# Main_Board.net
KiCad netlist of a schematic drawn in Altium Designer
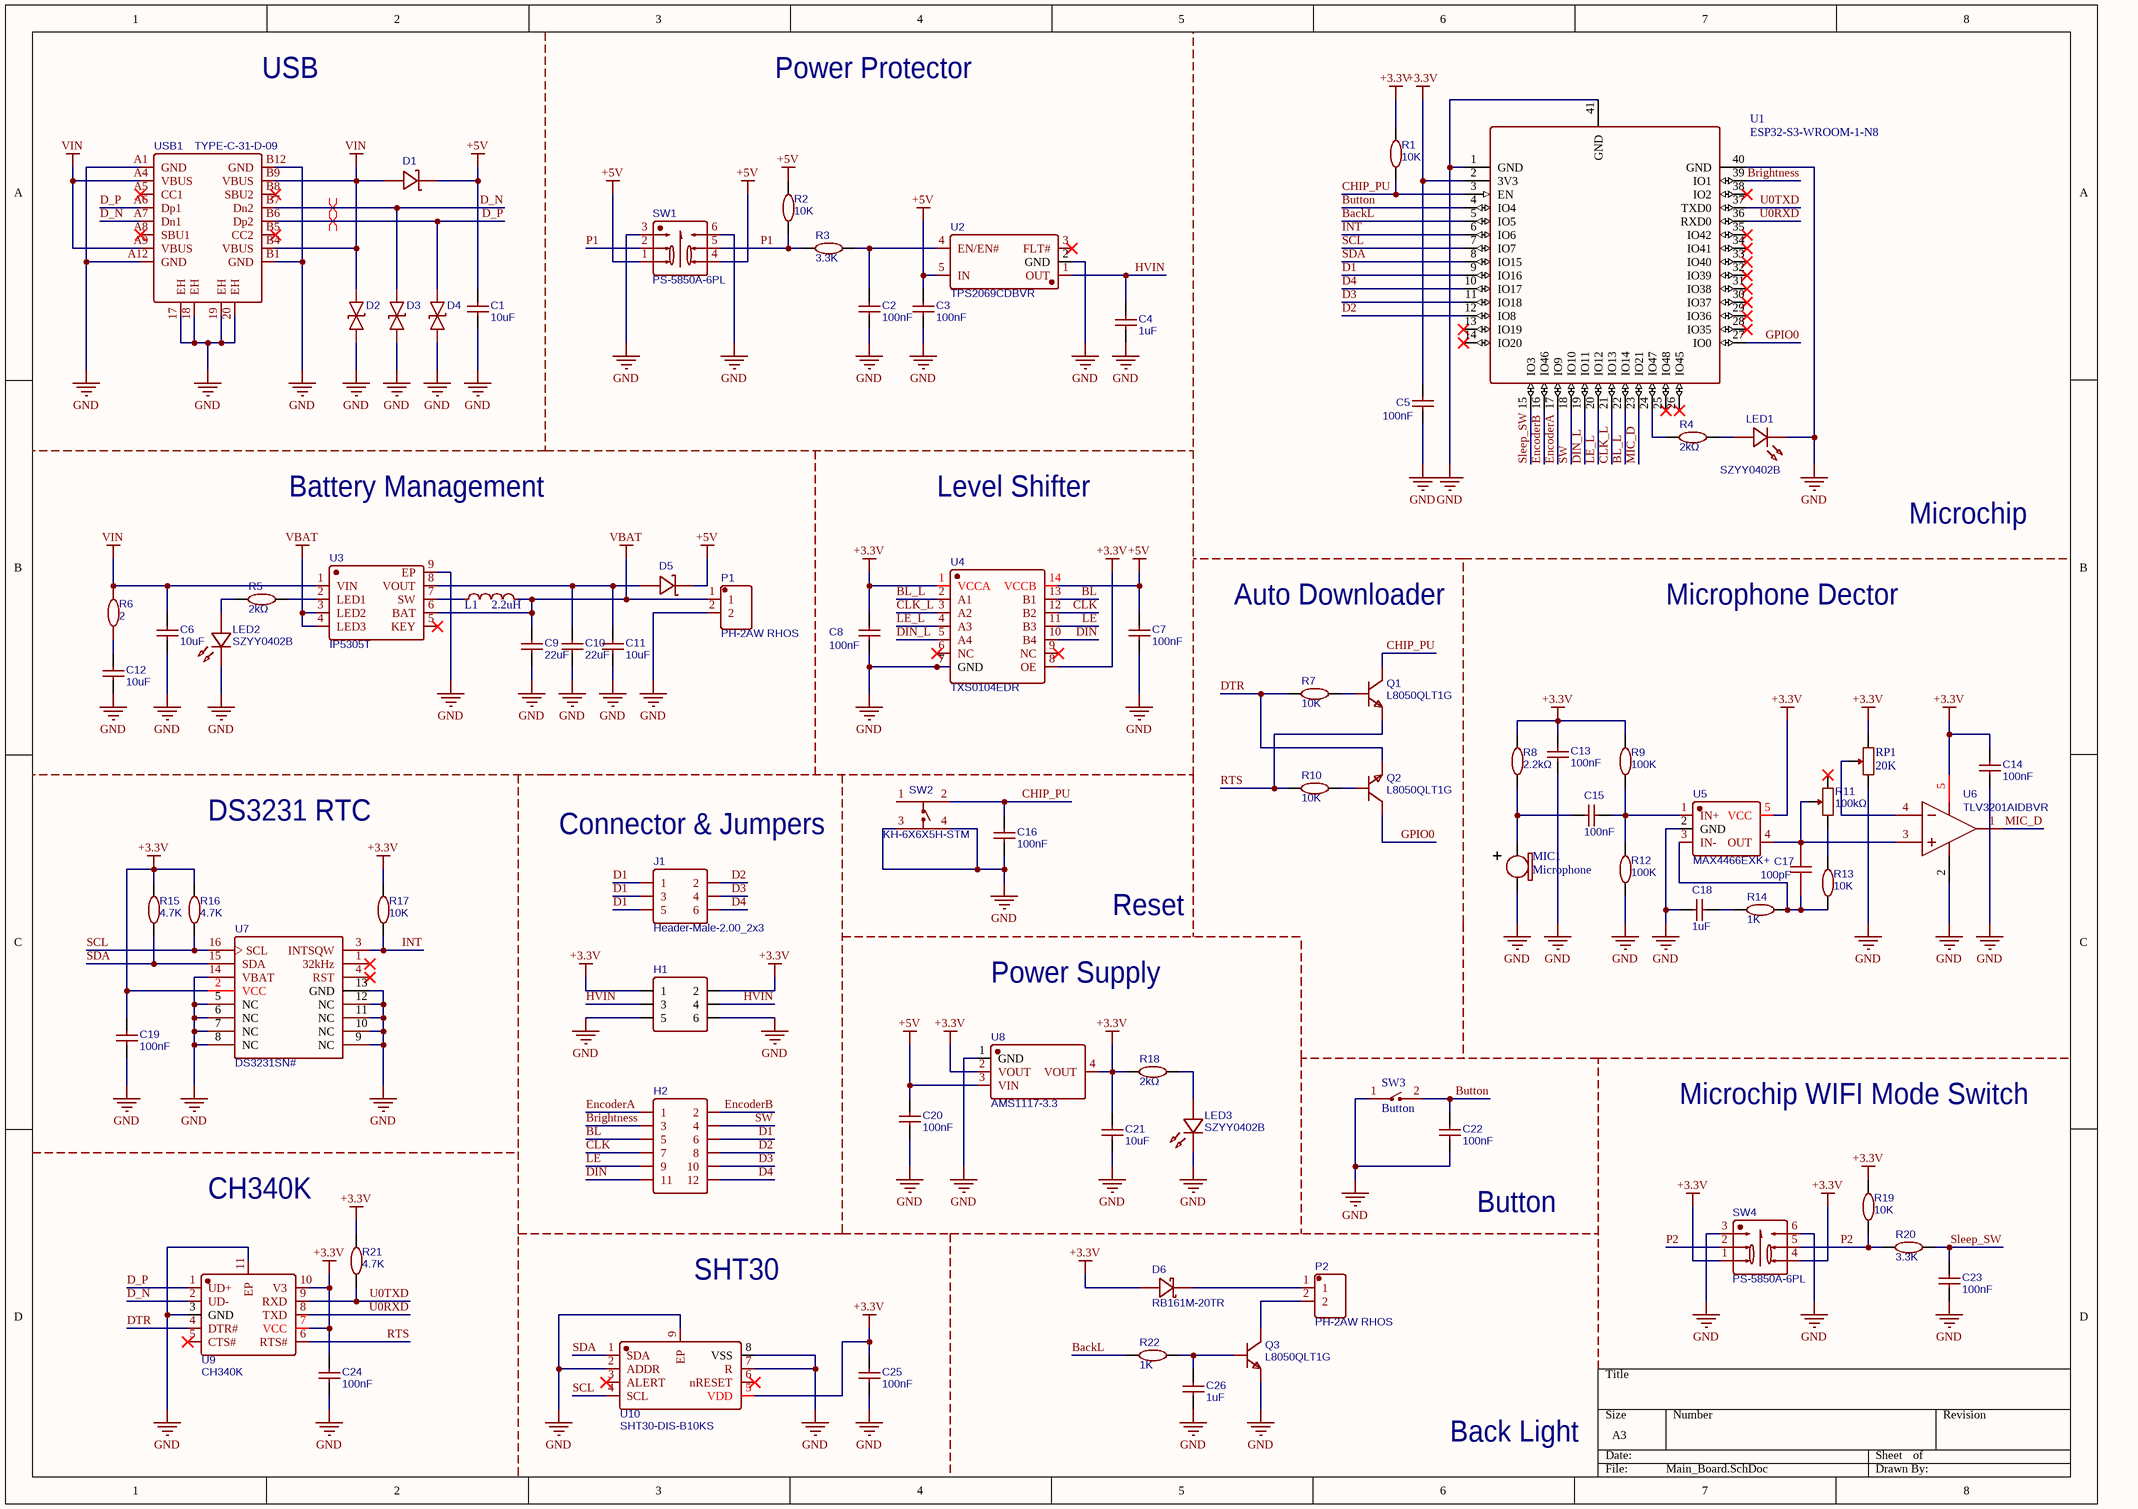
[diagram p0: Main_Board.SchDoc]

(export (version "E")
  (design (tool "Eeschema 10.0.6"))
  (components
    (comp (ref "C1")
      (value "10uF")
      (footprint "C0805")
      (fields
        (field (name "BOM_MANUFACTURER PART") "CL21A106KOQNNNE")
        (field (name "BOM_SUPPLIER PART") "C1713")
      )
      (libsource (lib "Regular_Components") (part "10uF"))
    )
    (comp (ref "C2")
      (value "100nF")
      (footprint "C0402_NEW")
      (fields
        (field (name "BOM_MANUFACTURER PART") "CL05B104KO5NNNC")
        (field (name "BOM_SUPPLIER PART") "C1525")
      )
      (libsource (lib "Regular_Components") (part "100nF"))
    )
    (comp (ref "C3")
      (value "100nF")
      (footprint "C0402_NEW")
      (fields
        (field (name "BOM_MANUFACTURER PART") "CL05B104KO5NNNC")
        (field (name "BOM_SUPPLIER PART") "C1525")
      )
      (libsource (lib "Regular_Components") (part "100nF"))
    )
    (comp (ref "C4")
      (value "1uF")
      (footprint "C0402")
      (fields
        (field (name "BOM_MANUFACTURER PART") "CL05A105KO5NNNC")
        (field (name "BOM_SUPPLIER PART") "C29266")
      )
      (libsource (lib "Regular_Components") (part "1uF"))
    )
    (comp (ref "C5")
      (value "100nF")
      (footprint "C0402_NEW")
      (fields
        (field (name "BOM_MANUFACTURER PART") "CL05B104KO5NNNC")
        (field (name "BOM_SUPPLIER PART") "C1525")
      )
      (libsource (lib "Regular_Components") (part "100nF"))
    )
    (comp (ref "C6")
      (value "10uF")
      (footprint "C0805")
      (fields
        (field (name "BOM_MANUFACTURER PART") "CL21A106KOQNNNE")
        (field (name "BOM_SUPPLIER PART") "C1713")
      )
      (libsource (lib "Regular_Components") (part "10uF"))
    )
    (comp (ref "C7")
      (value "100nF")
      (footprint "C0402_NEW")
      (fields
        (field (name "BOM_MANUFACTURER PART") "CL05B104KO5NNNC")
        (field (name "BOM_SUPPLIER PART") "C1525")
      )
      (libsource (lib "Regular_Components") (part "100nF"))
    )
    (comp (ref "C8")
      (value "100nF")
      (footprint "C0402_NEW")
      (fields
        (field (name "BOM_MANUFACTURER PART") "CL05B104KO5NNNC")
        (field (name "BOM_SUPPLIER PART") "C1525")
      )
      (libsource (lib "Regular_Components") (part "100nF"))
    )
    (comp (ref "C9")
      (value "22uF")
      (footprint "C0805")
      (fields
        (field (name "BOM_MANUFACTURER PART") "CL21A226MOQNNNE")
        (field (name "BOM_SUPPLIER PART") "C98190")
      )
      (libsource (lib "Regular_Components") (part "22uF"))
    )
    (comp (ref "C10")
      (value "22uF")
      (footprint "C0805")
      (fields
        (field (name "BOM_MANUFACTURER PART") "CL21A226MOQNNNE")
        (field (name "BOM_SUPPLIER PART") "C98190")
      )
      (libsource (lib "Regular_Components") (part "22uF"))
    )
    (comp (ref "C11")
      (value "10uF")
      (footprint "C0805")
      (fields
        (field (name "BOM_MANUFACTURER PART") "CL21A106KOQNNNE")
        (field (name "BOM_SUPPLIER PART") "C1713")
      )
      (libsource (lib "Regular_Components") (part "10uF"))
    )
    (comp (ref "C12")
      (value "10uF")
      (footprint "C0805")
      (fields
        (field (name "BOM_MANUFACTURER PART") "CL21A106KOQNNNE")
        (field (name "BOM_SUPPLIER PART") "C1713")
      )
      (libsource (lib "Regular_Components") (part "10uF"))
    )
    (comp (ref "C13")
      (value "100nF")
      (footprint "C0402_NEW")
      (fields
        (field (name "BOM_MANUFACTURER PART") "CL05B104KO5NNNC")
        (field (name "BOM_SUPPLIER PART") "C1525")
      )
      (libsource (lib "Regular_Components") (part "100nF"))
    )
    (comp (ref "C14")
      (value "100nF")
      (footprint "C0402_NEW")
      (fields
        (field (name "BOM_MANUFACTURER PART") "CL05B104KO5NNNC")
        (field (name "BOM_SUPPLIER PART") "C1525")
      )
      (libsource (lib "Regular_Components") (part "100nF"))
    )
    (comp (ref "C15")
      (value "100nF")
      (footprint "C0402_NEW")
      (fields
        (field (name "BOM_MANUFACTURER PART") "CL05B104KO5NNNC")
        (field (name "BOM_SUPPLIER PART") "C1525")
      )
      (libsource (lib "Regular_Components") (part "100nF"))
    )
    (comp (ref "C16")
      (value "100nF")
      (footprint "C0402_NEW")
      (fields
        (field (name "BOM_MANUFACTURER PART") "CL05B104KO5NNNC")
        (field (name "BOM_SUPPLIER PART") "C1525")
      )
      (libsource (lib "Regular_Components") (part "100nF"))
    )
    (comp (ref "C17")
      (value "100pF")
      (footprint "C0402")
      (fields
        (field (name "BOM_MANUFACTURER PART") "CC0402JRNPO9BN101")
        (field (name "BOM_SUPPLIER PART") "C106200")
      )
      (libsource (lib "Regular_Components") (part "100pF"))
    )
    (comp (ref "C18")
      (value "1uF")
      (footprint "C0402")
      (fields
        (field (name "BOM_MANUFACTURER PART") "CL05A105KO5NNNC")
        (field (name "BOM_SUPPLIER PART") "C29266")
      )
      (libsource (lib "Regular_Components") (part "1uF"))
    )
    (comp (ref "C19")
      (value "100nF")
      (footprint "C0402_NEW")
      (fields
        (field (name "BOM_MANUFACTURER PART") "CL05B104KO5NNNC")
        (field (name "BOM_SUPPLIER PART") "C1525")
      )
      (libsource (lib "Regular_Components") (part "100nF"))
    )
    (comp (ref "C20")
      (value "100nF")
      (footprint "C0402_NEW")
      (fields
        (field (name "BOM_MANUFACTURER PART") "CL05B104KO5NNNC")
        (field (name "BOM_SUPPLIER PART") "C1525")
      )
      (libsource (lib "Regular_Components") (part "100nF"))
    )
    (comp (ref "C21")
      (value "10uF")
      (footprint "C0805")
      (fields
        (field (name "BOM_MANUFACTURER PART") "CL21A106KOQNNNE")
        (field (name "BOM_SUPPLIER PART") "C1713")
      )
      (libsource (lib "Regular_Components") (part "10uF"))
    )
    (comp (ref "C22")
      (value "100nF")
      (footprint "C0402_NEW")
      (fields
        (field (name "BOM_MANUFACTURER PART") "CL05B104KO5NNNC")
        (field (name "BOM_SUPPLIER PART") "C1525")
      )
      (libsource (lib "Regular_Components") (part "100nF"))
    )
    (comp (ref "C23")
      (value "100nF")
      (footprint "C0402_NEW")
      (fields
        (field (name "BOM_MANUFACTURER PART") "CL05B104KO5NNNC")
        (field (name "BOM_SUPPLIER PART") "C1525")
      )
      (libsource (lib "Regular_Components") (part "100nF"))
    )
    (comp (ref "C24")
      (value "100nF")
      (footprint "C0402_NEW")
      (fields
        (field (name "BOM_MANUFACTURER PART") "CL05B104KO5NNNC")
        (field (name "BOM_SUPPLIER PART") "C1525")
      )
      (libsource (lib "Regular_Components") (part "100nF"))
    )
    (comp (ref "C25")
      (value "100nF")
      (footprint "C0402_NEW")
      (fields
        (field (name "BOM_MANUFACTURER PART") "CL05B104KO5NNNC")
        (field (name "BOM_SUPPLIER PART") "C1525")
      )
      (libsource (lib "Regular_Components") (part "100nF"))
    )
    (comp (ref "C26")
      (value "1uF")
      (footprint "C0402")
      (fields
        (field (name "BOM_MANUFACTURER PART") "CL05A105KO5NNNC")
        (field (name "BOM_SUPPLIER PART") "C29266")
      )
      (libsource (lib "Regular_Components") (part "1uF"))
    )
    (comp (ref "D1")
      (value "SS54_C22452")
      (footprint "SMA_L4.4-W2.8-LS5.4-R-RD")
      (fields (field (name "BOM_MANUFACTURER PART") "SS54") (field (name "BOM_SUPPLIER PART") "C22452"))
      (libsource (lib "Regular_Components") (part "SS54_C22452"))
    )
    (comp (ref "D2")
      (value "LESD5D5.0CT1G")
      (footprint "SOD-523_L1.2-W0.8-LS1.6-BI")
      (fields (field (name "BOM_SUPPLIER PART") "C383211") (field (name "CONTRIBUTOR") "LCSC"))
      (libsource (lib "Regular_Components") (part "LESD5D5.0CT1G"))
    )
    (comp (ref "D3")
      (value "LESD5D5.0CT1G")
      (footprint "SOD-523_L1.2-W0.8-LS1.6-BI")
      (fields (field (name "BOM_SUPPLIER PART") "C383211") (field (name "CONTRIBUTOR") "LCSC"))
      (libsource (lib "Regular_Components") (part "LESD5D5.0CT1G"))
    )
    (comp (ref "D4")
      (value "LESD5D5.0CT1G")
      (footprint "SOD-523_L1.2-W0.8-LS1.6-BI")
      (fields (field (name "BOM_SUPPLIER PART") "C383211") (field (name "CONTRIBUTOR") "LCSC"))
      (libsource (lib "Regular_Components") (part "LESD5D5.0CT1G"))
    )
    (comp (ref "D5")
      (value "SS54_C22452")
      (footprint "SMA_L4.4-W2.8-LS5.4-R-RD")
      (fields (field (name "BOM_MANUFACTURER PART") "SS54") (field (name "BOM_SUPPLIER PART") "C22452"))
      (libsource (lib "Regular_Components") (part "SS54_C22452"))
    )
    (comp (ref "D6")
      (value "RB161M-20TR")
      (footprint "SOD-123_L2.6-W1.6-LS3.5-RD-1")
      (fields (field (name "BOM_SUPPLIER PART") "C427072") (field (name "CONTRIBUTOR") "LCSC"))
      (libsource (lib "Regular_Components") (part "RB161M-20TR"))
    )
    (comp (ref "H1")
      (value "Header-Female-2.54_2x3")
      (footprint "HDR-TH_6P-P2.54-V-F-R2-C3-S2.54")
      (fields
        (field (name "BOM_MANUFACTURER PART") "DS1023-2*3SF11")
        (field (name "BOM_SUPPLIER PART") "C92272")
        (field (name "CONTRIBUTOR") "LCSC")
      )
      (libsource (lib "Regular_Components") (part "Header-Female-2.54_2x3"))
    )
    (comp (ref "H2")
      (value "Header-Female-2.54_2x6")
      (footprint "HDR-TH_12P-P2.54-V-F-R2-C6-S2.54")
      (fields (field (name "BOM_MANUFACTURER PART") "2.54-2*6P母") (field (name "BOM_SUPPLIER PART") "C36191"))
      (libsource (lib "Regular_Components") (part "Header-Female-2.54_2x6"))
    )
    (comp (ref "J1")
      (value "Header-Male-2.00_2x3")
      (footprint "HDR2.0-LI-2X3P")
      (libsource (lib "Regular_Components") (part "Header-Male-2.00_2x3"))
    )
    (comp (ref "L1")
      (value "2.2uH")
      (footprint "L_2.2uH")
      (libsource (lib "Regular_Components") (part "2.2uH"))
    )
    (comp (ref "LED1")
      (value "SZYY0402B")
      (footprint "LED0402-RD_BLUE")
      (fields (field (name "BOM_SUPPLIER PART") "C434447") (field (name "CONTRIBUTOR") "LCSC"))
      (libsource (lib "Regular_Components") (part "SZYY0402B"))
    )
    (comp (ref "LED2")
      (value "SZYY0402B")
      (footprint "LED0402-RD_BLUE")
      (fields (field (name "BOM_SUPPLIER PART") "C434447") (field (name "CONTRIBUTOR") "LCSC"))
      (libsource (lib "Regular_Components") (part "SZYY0402B"))
    )
    (comp (ref "LED3")
      (value "SZYY0402B")
      (footprint "LED0402-RD_BLUE")
      (fields (field (name "BOM_SUPPLIER PART") "C434447") (field (name "CONTRIBUTOR") "LCSC"))
      (libsource (lib "Regular_Components") (part "SZYY0402B"))
    )
    (comp (ref "MIC1")
      (value "Microphone")
      (footprint "Microphone")
      (libsource (lib "Regular_Components") (part "Microphone"))
    )
    (comp (ref "P1")
      (value "PH-2AW RHOS")
      (footprint "CONN-TH_2P-P2.00_PH-2AW")
      (fields (field (name "BOM_SUPPLIER PART") "C16965"))
      (libsource (lib "Regular_Components") (part "PH-2AW RHOS"))
    )
    (comp (ref "P2")
      (value "PH-2AW RHOS")
      (footprint "CONN-TH_2P-P2.00_PH-2AW")
      (fields (field (name "BOM_SUPPLIER PART") "C16965"))
      (libsource (lib "Regular_Components") (part "PH-2AW RHOS"))
    )
    (comp (ref "Q1")
      (value "L8050QLT1G")
      (footprint "SOT-23-3_L2.9-W1.3-P1.90-LS2.4-BR")
      (fields (field (name "BOM_SUPPLIER PART") "C49581"))
      (libsource (lib "Regular_Components") (part "L8050QLT1G"))
    )
    (comp (ref "Q2")
      (value "L8050QLT1G")
      (footprint "SOT-23-3_L2.9-W1.3-P1.90-LS2.4-BR")
      (fields (field (name "BOM_SUPPLIER PART") "C49581"))
      (libsource (lib "Regular_Components") (part "L8050QLT1G"))
    )
    (comp (ref "Q3")
      (value "L8050QLT1G")
      (footprint "SOT-23-3_L2.9-W1.3-P1.90-LS2.4-BR")
      (fields (field (name "BOM_SUPPLIER PART") "C49581"))
      (libsource (lib "Regular_Components") (part "L8050QLT1G"))
    )
    (comp (ref "R1")
      (value "10K")
      (footprint "R0402")
      (fields
        (field (name "BOM_MANUFACTURER PART") "RC0402FR-0710KL")
        (field (name "BOM_SUPPLIER PART") "C60490")
      )
      (libsource (lib "Regular_Components") (part "10K"))
    )
    (comp (ref "R2")
      (value "10K")
      (footprint "R0402")
      (fields
        (field (name "BOM_MANUFACTURER PART") "RC0402FR-0710KL")
        (field (name "BOM_SUPPLIER PART") "C60490")
      )
      (libsource (lib "Regular_Components") (part "10K"))
    )
    (comp (ref "R3")
      (value "3.3K")
      (footprint "R0402")
      (fields
        (field (name "BOM_MANUFACTURER PART") "RC0402FR-073K3L")
        (field (name "BOM_SUPPLIER PART") "C137992")
      )
      (libsource (lib "Regular_Components") (part "3.3K"))
    )
    (comp (ref "R4")
      (value "2kΩ")
      (footprint "R0402")
      (fields
        (field (name "BOM_MANUFACTURER PART") "0402WGF2001TCE")
        (field (name "BOM_SUPPLIER PART") "C4109")
      )
      (libsource (lib "Regular_Components") (part "2kΩ"))
    )
    (comp (ref "R5")
      (value "2kΩ")
      (footprint "R0402")
      (fields
        (field (name "BOM_MANUFACTURER PART") "0402WGF2001TCE")
        (field (name "BOM_SUPPLIER PART") "C4109")
      )
      (libsource (lib "Regular_Components") (part "2kΩ"))
    )
    (comp (ref "R6")
      (value "2")
      (footprint "R0603")
      (fields
        (field (name "BOM_SUPPLIER PART") "C185341")
        (field (name "BOM_MANUFACTURER PART") "RC0603FR-072RL")
        (field (name "CONTRIBUTOR") "LCSC")
      )
      (libsource (lib "Regular_Components") (part "2"))
    )
    (comp (ref "R7")
      (value "10K")
      (footprint "R0402")
      (fields
        (field (name "BOM_MANUFACTURER PART") "RC0402FR-0710KL")
        (field (name "BOM_SUPPLIER PART") "C60490")
      )
      (libsource (lib "Regular_Components") (part "10K"))
    )
    (comp (ref "R8")
      (value "2.2kΩ")
      (footprint "R0402")
      (fields
        (field (name "BOM_MANUFACTURER PART") "0402WGF2001TCE")
        (field (name "BOM_SUPPLIER PART") "C4109")
      )
      (libsource (lib "Regular_Components") (part "2kΩ"))
    )
    (comp (ref "R9")
      (value "100K")
      (footprint "R0402")
      (fields
        (field (name "BOM_MANUFACTURER PART") "RC0402FR-07100KL")
        (field (name "BOM_SUPPLIER PART") "C60491")
      )
      (libsource (lib "Regular_Components") (part "100K"))
    )
    (comp (ref "R10")
      (value "10K")
      (footprint "R0402")
      (fields
        (field (name "BOM_MANUFACTURER PART") "RC0402FR-0710KL")
        (field (name "BOM_SUPPLIER PART") "C60490")
      )
      (libsource (lib "Regular_Components") (part "10K"))
    )
    (comp (ref "R11")
      (value "100kΩ")
      (footprint "RES-ADJ-SMD_VG039NCH")
      (fields
        (field (name "BOM_MANUFACTURER PART") "VG039NCHXTB104")
        (field (name "BOM_SUPPLIER PART") "C128545")
        (field (name "CONTRIBUTOR") "LCSC")
      )
      (libsource (lib "Regular_Components") (part "RP-VG039NCHXTB104"))
    )
    (comp (ref "R12")
      (value "100K")
      (footprint "R0402")
      (fields
        (field (name "BOM_MANUFACTURER PART") "RC0402FR-07100KL")
        (field (name "BOM_SUPPLIER PART") "C60491")
      )
      (libsource (lib "Regular_Components") (part "100K"))
    )
    (comp (ref "R13")
      (value "10K")
      (footprint "R0402")
      (fields
        (field (name "BOM_MANUFACTURER PART") "RC0402FR-0710KL")
        (field (name "BOM_SUPPLIER PART") "C60490")
      )
      (libsource (lib "Regular_Components") (part "10K"))
    )
    (comp (ref "R14")
      (value "1K")
      (footprint "R0402")
      (fields
        (field (name "BOM_MANUFACTURER PART") "RC0402FR-071KL")
        (field (name "BOM_SUPPLIER PART") "C106235")
      )
      (libsource (lib "Regular_Components") (part "1K"))
    )
    (comp (ref "R15")
      (value "4.7K")
      (footprint "R0402")
      (fields
        (field (name "BOM_MANUFACTURER PART") "RC0402FR-074K7L")
        (field (name "BOM_SUPPLIER PART") "C105871")
      )
      (libsource (lib "Regular_Components") (part "4.7K"))
    )
    (comp (ref "R16")
      (value "4.7K")
      (footprint "R0402")
      (fields
        (field (name "BOM_MANUFACTURER PART") "RC0402FR-074K7L")
        (field (name "BOM_SUPPLIER PART") "C105871")
      )
      (libsource (lib "Regular_Components") (part "4.7K"))
    )
    (comp (ref "R17")
      (value "10K")
      (footprint "R0402")
      (fields
        (field (name "BOM_MANUFACTURER PART") "RC0402FR-0710KL")
        (field (name "BOM_SUPPLIER PART") "C60490")
      )
      (libsource (lib "Regular_Components") (part "10K"))
    )
    (comp (ref "R18")
      (value "2kΩ")
      (footprint "R0402")
      (fields
        (field (name "BOM_MANUFACTURER PART") "0402WGF2001TCE")
        (field (name "BOM_SUPPLIER PART") "C4109")
      )
      (libsource (lib "Regular_Components") (part "2kΩ"))
    )
    (comp (ref "R19")
      (value "10K")
      (footprint "R0402")
      (fields
        (field (name "BOM_MANUFACTURER PART") "RC0402FR-0710KL")
        (field (name "BOM_SUPPLIER PART") "C60490")
      )
      (libsource (lib "Regular_Components") (part "10K"))
    )
    (comp (ref "R20")
      (value "3.3K")
      (footprint "R0402")
      (fields
        (field (name "BOM_MANUFACTURER PART") "RC0402FR-073K3L")
        (field (name "BOM_SUPPLIER PART") "C137992")
      )
      (libsource (lib "Regular_Components") (part "3.3K"))
    )
    (comp (ref "R21")
      (value "4.7K")
      (footprint "R0402")
      (fields
        (field (name "BOM_MANUFACTURER PART") "RC0402FR-074K7L")
        (field (name "BOM_SUPPLIER PART") "C105871")
      )
      (libsource (lib "Regular_Components") (part "4.7K"))
    )
    (comp (ref "R22")
      (value "1K")
      (footprint "R0402")
      (fields
        (field (name "BOM_MANUFACTURER PART") "RC0402FR-071KL")
        (field (name "BOM_SUPPLIER PART") "C106235")
      )
      (libsource (lib "Regular_Components") (part "1K"))
    )
    (comp (ref "RP1")
      (value "20K")
      (footprint "RES-ADJ-SMD_VG039NCH")
      (fields (field (name "版权归属") "源创客"))
      (libsource (lib "Regular_Components") (part "RP-VG039NCHXTB203"))
    )
    (comp (ref "SW1")
      (value "PS-5850A-6PL")
      (footprint "SW-TH_6P-L5.8-W5.8-P2.00-LS4.5-BL")
      (fields (field (name "BOM_SUPPLIER PART") "C963201") (field (name "CONTRIBUTOR") "LCSC"))
      (libsource (lib "Regular_Components") (part "PS-5850A-6PL"))
    )
    (comp (ref "SW2")
      (value "KH-6X6X5H-STM")
      (footprint "SW-SMD_4P-L6.0-W6.0-P4.50-LS9.0-2")
      (fields (field (name "BOM_SUPPLIER PART") "C2837531") (field (name "CONTRIBUTOR") "LCSC"))
      (libsource (lib "Regular_Components") (part "KH-6X6X5H-STM"))
    )
    (comp (ref "SW3")
      (value "Button")
      (footprint "Button")
      (libsource (lib "Regular_Components") (part "Button"))
    )
    (comp (ref "SW4")
      (value "PS-5850A-6PL")
      (footprint "SW-TH_6P-L5.8-W5.8-P2.00-LS4.5-BL")
      (fields (field (name "BOM_SUPPLIER PART") "C963201") (field (name "CONTRIBUTOR") "LCSC"))
      (libsource (lib "Regular_Components") (part "PS-5850A-6PL"))
    )
    (comp (ref "U1")
      (value "ESP32-S3-WROOM-1-N8")
      (footprint "ESP32-S3-WROOM-1-N8_EXP")
      (fields (field (name "COPYRIGHT") "Copyright (C) 2023 Ultra Librarian. All rights reserved."))
      (libsource (lib "Regular_Components") (part "ESP32-S3-WROOM-1-N8"))
    )
    (comp (ref "U2")
      (value "TPS2069CDBVR")
      (footprint "SOT-23-5_L3.0-W1.7-P0.95-LS2.8-BR")
      (fields (field (name "BOM_SUPPLIER PART") "C181752") (field (name "CONTRIBUTOR") "LCSC"))
      (libsource (lib "Regular_Components") (part "TPS2069CDBVR"))
    )
    (comp (ref "U3")
      (value "IP5305T")
      (footprint "ESOP-8_L4.9-W3.9-P1.27-LS6.0-BL-EP")
      (fields (field (name "BOM_SUPPLIER PART") "C2982924") (field (name "CONTRIBUTOR") "LCSC"))
      (libsource (lib "Regular_Components") (part "IP5305T"))
    )
    (comp (ref "U4")
      (value "TXS0104EDR")
      (footprint "SOIC-14_L8.7-W3.9-P1.27-LS6.0-BL")
      (fields (field (name "BOM_SUPPLIER PART") "C79342") (field (name "CONTRIBUTOR") "LCSC"))
      (libsource (lib "Regular_Components") (part "TXS0104EDR"))
    )
    (comp (ref "U5")
      (value "MAX4466EXK+")
      (footprint "SC-70-5_L2.0-W1.3-P0.65-LS2.2-BL")
      (fields (field (name "BOM_SUPPLIER PART") "C2892801") (field (name "CONTRIBUTOR") "LCSC"))
      (libsource (lib "Regular_Components") (part "MAX4466EXK+"))
    )
    (comp (ref "U6")
      (value "TLV3201AIDBVR")
      (footprint "SOT-23-5_L3.0-W1.7-P0.95-LS2.8-BR")
      (fields (field (name "BOM_SUPPLIER PART") "C105188"))
      (libsource (lib "Regular_Components") (part "TLV3201AIDBVR"))
    )
    (comp (ref "U7")
      (value "DS3231SN#")
      (footprint "SOIC-16_L10.3-W7.5-P1.27-LS10.3-BL")
      (fields
        (field (name "BOM_SUPPLIER PART") "C9866")
        (field (name "BOM_MANUFACTURER PART") "DS3231SN#T&R")
        (field (name "SUBPART_NO") "1")
      )
      (libsource (lib "Regular_Components") (part "DS3231SN#"))
    )
    (comp (ref "U8")
      (value "AMS1117-3.3")
      (footprint "SOT-223-3_L6.5-W3.4-P2.30-LS7.0-BR")
      (fields (field (name "BOM_SUPPLIER PART") "C6186"))
      (libsource (lib "Regular_Components") (part "AMS1117-3.3"))
    )
    (comp (ref "U9")
      (value "CH340K")
      (footprint "ESOP-10_L4.9-W3.9-P1.00-LS6.2-BL-EP")
      (fields (field (name "BOM_SUPPLIER PART") "C968586") (field (name "CONTRIBUTOR") "LCSC"))
      (libsource (lib "Regular_Components") (part "CH340K"))
    )
    (comp (ref "U10")
      (value "SHT30-DIS-B10KS")
      (footprint "DFN-8_L2.5-W2.5-P0.50-BL-EP")
      (fields (field (name "BOM_SUPPLIER PART") "C2687423") (field (name "CONTRIBUTOR") "LCSC"))
      (libsource (lib "Regular_Components") (part "SHT30-DIS-B10KS"))
    )
    (comp (ref "USB1")
      (value "TYPE-C-31-D-09")
      (footprint "USB-C-TH_TYPE-C-31-D-09")
      (fields (field (name "BOM_SUPPLIER PART") "C2848615") (field (name "CONTRIBUTOR") "LCSC"))
      (libsource (lib "Regular_Components") (part "TYPE-C-31-D-09"))
    )
  )
  (nets
    (net (code "1") (name "+3.3V") (class "Default")
      (node (ref "C13") (pin "2") (pinfunction "2_2") (pintype "passive"))
      (node (ref "C14") (pin "2") (pinfunction "2_2") (pintype "passive"))
      (node (ref "C19") (pin "2") (pinfunction "2_2") (pintype "passive"))
      (node (ref "C21") (pin "2") (pinfunction "2_2") (pintype "passive"))
      (node (ref "C24") (pin "2") (pinfunction "2_2") (pintype "passive"))
      (node (ref "C25") (pin "2") (pinfunction "2_2") (pintype "passive"))
      (node (ref "C5") (pin "2") (pinfunction "2_2") (pintype "passive"))
      (node (ref "C8") (pin "2") (pinfunction "2_2") (pintype "passive"))
      (node (ref "D6") (pin "2") (pinfunction "A_2") (pintype "passive"))
      (node (ref "H1") (pin "1") (pinfunction "1_1") (pintype "passive"))
      (node (ref "H1") (pin "2") (pinfunction "2_2") (pintype "passive"))
      (node (ref "R1") (pin "2") (pinfunction "2_2") (pintype "passive"))
      (node (ref "R15") (pin "2") (pinfunction "2_2") (pintype "passive"))
      (node (ref "R16") (pin "2") (pinfunction "2_2") (pintype "passive"))
      (node (ref "R17") (pin "2") (pinfunction "2_2") (pintype "passive"))
      (node (ref "R18") (pin "1") (pinfunction "1_1") (pintype "passive"))
      (node (ref "R19") (pin "2") (pinfunction "2_2") (pintype "passive"))
      (node (ref "R21") (pin "2") (pinfunction "2_2") (pintype "passive"))
      (node (ref "R8") (pin "2") (pinfunction "2_2") (pintype "passive"))
      (node (ref "R9") (pin "2") (pinfunction "2_2") (pintype "passive"))
      (node (ref "RP1") (pin "1") (pinfunction "1_1") (pintype "passive"))
      (node (ref "SW4") (pin "1") (pinfunction "1_1") (pintype "passive"))
      (node (ref "SW4") (pin "4") (pinfunction "4_4") (pintype "passive"))
      (node (ref "U1") (pin "2") (pinfunction "3V3_2") (pintype "power_in"))
      (node (ref "U10") (pin "5") (pinfunction "VDD_5") (pintype "passive"))
      (node (ref "U4") (pin "1") (pinfunction "VCCA_1") (pintype "passive"))
      (node (ref "U4") (pin "8") (pinfunction "OE_8") (pintype "passive"))
      (node (ref "U5") (pin "5") (pinfunction "VCC_5") (pintype "passive"))
      (node (ref "U6") (pin "5") (pinfunction "VCC_5") (pintype "passive"))
      (node (ref "U7") (pin "2") (pinfunction "VCC_2") (pintype "passive"))
      (node (ref "U8") (pin "2") (pinfunction "VOUT_2") (pintype "passive"))
      (node (ref "U8") (pin "4") (pinfunction "VOUT_4") (pintype "passive"))
      (node (ref "U9") (pin "10") (pinfunction "V3_10") (pintype "passive"))
      (node (ref "U9") (pin "7") (pinfunction "VCC_7") (pintype "passive"))
    )
    (net (code "2") (name "+5V") (class "Default")
      (node (ref "C1") (pin "2") (pinfunction "2_2") (pintype "passive"))
      (node (ref "C20") (pin "2") (pinfunction "2_2") (pintype "passive"))
      (node (ref "C3") (pin "2") (pinfunction "2_2") (pintype "passive"))
      (node (ref "C7") (pin "2") (pinfunction "2_2") (pintype "passive"))
      (node (ref "D1") (pin "2") (pinfunction "K_2") (pintype "passive"))
      (node (ref "D5") (pin "2") (pinfunction "K_2") (pintype "passive"))
      (node (ref "R2") (pin "2") (pinfunction "2_2") (pintype "passive"))
      (node (ref "SW1") (pin "1") (pinfunction "1_1") (pintype "passive"))
      (node (ref "SW1") (pin "4") (pinfunction "4_4") (pintype "passive"))
      (node (ref "U2") (pin "5") (pinfunction "IN_5") (pintype "passive"))
      (node (ref "U4") (pin "14") (pinfunction "VCCB_14") (pintype "passive"))
      (node (ref "U8") (pin "3") (pinfunction "VIN_3") (pintype "passive"))
    )
    (net (code "3") (name "/BL") (class "Default")
      (node (ref "H2") (pin "5") (pinfunction "5_5") (pintype "passive"))
      (node (ref "U4") (pin "13") (pinfunction "B1_13") (pintype "passive"))
    )
    (net (code "4") (name "/BL_L") (class "Default")
      (node (ref "U1") (pin "22") (pinfunction "IO14_22") (pintype "bidirectional"))
      (node (ref "U4") (pin "2") (pinfunction "A1_2") (pintype "passive"))
    )
    (net (code "5") (name "/BackL") (class "Default")
      (node (ref "R22") (pin "1") (pinfunction "1_1") (pintype "passive"))
      (node (ref "U1") (pin "5") (pinfunction "IO5_5") (pintype "bidirectional"))
    )
    (net (code "6") (name "/Brightness") (class "Default")
      (node (ref "H2") (pin "3") (pinfunction "3_3") (pintype "passive"))
      (node (ref "U1") (pin "39") (pinfunction "IO1_39") (pintype "bidirectional"))
    )
    (net (code "7") (name "/Button") (class "Default")
      (node (ref "C22") (pin "2") (pinfunction "2_2") (pintype "passive"))
      (node (ref "SW3") (pin "2") (pinfunction "2_2") (pintype "passive"))
      (node (ref "U1") (pin "4") (pinfunction "IO4_4") (pintype "bidirectional"))
    )
    (net (code "8") (name "/CHIP_PU") (class "Default")
      (node (ref "C16") (pin "2") (pinfunction "2_2") (pintype "passive"))
      (node (ref "Q1") (pin "3") (pinfunction "C_3") (pintype "passive"))
      (node (ref "R1") (pin "1") (pinfunction "1_1") (pintype "passive"))
      (node (ref "SW2") (pin "2") (pinfunction "2_2") (pintype "passive"))
      (node (ref "U1") (pin "3") (pinfunction "EN_3") (pintype "input"))
    )
    (net (code "9") (name "/CLK") (class "Default")
      (node (ref "H2") (pin "7") (pinfunction "7_7") (pintype "passive"))
      (node (ref "U4") (pin "12") (pinfunction "B2_12") (pintype "passive"))
    )
    (net (code "10") (name "/CLK_L") (class "Default")
      (node (ref "U1") (pin "21") (pinfunction "IO13_21") (pintype "bidirectional"))
      (node (ref "U4") (pin "3") (pinfunction "A2_3") (pintype "passive"))
    )
    (net (code "11") (name "/D1") (class "Default")
      (node (ref "H2") (pin "6") (pinfunction "6_6") (pintype "passive"))
      (node (ref "J1") (pin "1") (pinfunction "1_1") (pintype "passive"))
      (node (ref "J1") (pin "3") (pinfunction "3_3") (pintype "passive"))
      (node (ref "J1") (pin "5") (pinfunction "5_5") (pintype "passive"))
      (node (ref "U1") (pin "9") (pinfunction "IO16_9") (pintype "bidirectional"))
    )
    (net (code "12") (name "/D2") (class "Default")
      (node (ref "H2") (pin "8") (pinfunction "8_8") (pintype "passive"))
      (node (ref "J1") (pin "2") (pinfunction "2_2") (pintype "passive"))
      (node (ref "U1") (pin "12") (pinfunction "IO8_12") (pintype "bidirectional"))
    )
    (net (code "13") (name "/D3") (class "Default")
      (node (ref "H2") (pin "10") (pinfunction "10_10") (pintype "passive"))
      (node (ref "J1") (pin "4") (pinfunction "4_4") (pintype "passive"))
      (node (ref "U1") (pin "11") (pinfunction "IO18_11") (pintype "bidirectional"))
    )
    (net (code "14") (name "/D4") (class "Default")
      (node (ref "H2") (pin "12") (pinfunction "12_12") (pintype "passive"))
      (node (ref "J1") (pin "6") (pinfunction "6_6") (pintype "passive"))
      (node (ref "U1") (pin "10") (pinfunction "IO17_10") (pintype "bidirectional"))
    )
    (net (code "15") (name "/DIN") (class "Default")
      (node (ref "H2") (pin "11") (pinfunction "11_11") (pintype "passive"))
      (node (ref "U4") (pin "10") (pinfunction "B4_10") (pintype "passive"))
    )
    (net (code "16") (name "/DIN_L") (class "Default")
      (node (ref "U1") (pin "19") (pinfunction "IO11_19") (pintype "bidirectional"))
      (node (ref "U4") (pin "5") (pinfunction "A4_5") (pintype "passive"))
    )
    (net (code "17") (name "/DTR") (class "Default")
      (node (ref "Q2") (pin "2") (pinfunction "E_2") (pintype "passive"))
      (node (ref "R7") (pin "1") (pinfunction "1_1") (pintype "passive"))
      (node (ref "U9") (pin "4") (pinfunction "DTR#_4") (pintype "passive"))
    )
    (net (code "18") (name "/D_N") (class "Default")
      (node (ref "D3") (pin "2") (pinfunction "2_2") (pintype "passive"))
      (node (ref "U9") (pin "2") (pinfunction "UD-_2") (pintype "passive"))
      (node (ref "USB1") (pin "A7") (pinfunction "Dn1_A7") (pintype "passive"))
      (node (ref "USB1") (pin "B7") (pinfunction "Dn2_B7") (pintype "passive"))
    )
    (net (code "19") (name "/D_P") (class "Default")
      (node (ref "D4") (pin "2") (pinfunction "2_2") (pintype "passive"))
      (node (ref "U9") (pin "1") (pinfunction "UD+_1") (pintype "passive"))
      (node (ref "USB1") (pin "A6") (pinfunction "Dp1_A6") (pintype "passive"))
      (node (ref "USB1") (pin "B6") (pinfunction "Dp2_B6") (pintype "passive"))
    )
    (net (code "20") (name "/EncoderA") (class "Default")
      (node (ref "H2") (pin "1") (pinfunction "1_1") (pintype "passive"))
      (node (ref "U1") (pin "17") (pinfunction "IO9_17") (pintype "bidirectional"))
    )
    (net (code "21") (name "/EncoderB") (class "Default")
      (node (ref "H2") (pin "2") (pinfunction "2_2") (pintype "passive"))
      (node (ref "U1") (pin "16") (pinfunction "IO46_16") (pintype "bidirectional"))
    )
    (net (code "22") (name "/GPIO0") (class "Default")
      (node (ref "Q2") (pin "3") (pinfunction "C_3") (pintype "passive"))
      (node (ref "U1") (pin "27") (pinfunction "IO0_27") (pintype "bidirectional"))
    )
    (net (code "23") (name "/HVIN") (class "Default")
      (node (ref "C4") (pin "2") (pinfunction "2_2") (pintype "passive"))
      (node (ref "H1") (pin "3") (pinfunction "3_3") (pintype "passive"))
      (node (ref "H1") (pin "4") (pinfunction "4_4") (pintype "passive"))
      (node (ref "U2") (pin "1") (pinfunction "OUT_1") (pintype "passive"))
    )
    (net (code "24") (name "/INT") (class "Default")
      (node (ref "R17") (pin "1") (pinfunction "1_1") (pintype "passive"))
      (node (ref "U1") (pin "6") (pinfunction "IO6_6") (pintype "bidirectional"))
      (node (ref "U7") (pin "3") (pinfunction "INTSQW_3") (pintype "passive"))
    )
    (net (code "25") (name "/LE") (class "Default")
      (node (ref "H2") (pin "9") (pinfunction "9_9") (pintype "passive"))
      (node (ref "U4") (pin "11") (pinfunction "B3_11") (pintype "passive"))
    )
    (net (code "26") (name "/LE_L") (class "Default")
      (node (ref "U1") (pin "20") (pinfunction "IO12_20") (pintype "bidirectional"))
      (node (ref "U4") (pin "4") (pinfunction "A3_4") (pintype "passive"))
    )
    (net (code "27") (name "/MIC_D") (class "Default")
      (node (ref "U1") (pin "23") (pinfunction "IO21_23") (pintype "bidirectional"))
      (node (ref "U6") (pin "1") (pinfunction "OUT_1") (pintype "passive"))
    )
    (net (code "28") (name "/P1") (class "Default")
      (node (ref "R2") (pin "1") (pinfunction "1_1") (pintype "passive"))
      (node (ref "R3") (pin "2") (pinfunction "2_2") (pintype "passive"))
      (node (ref "SW1") (pin "2") (pinfunction "2_2") (pintype "passive"))
      (node (ref "SW1") (pin "5") (pinfunction "5_5") (pintype "passive"))
    )
    (net (code "29") (name "/P2") (class "Default")
      (node (ref "R19") (pin "1") (pinfunction "1_1") (pintype "passive"))
      (node (ref "R20") (pin "2") (pinfunction "2_2") (pintype "passive"))
      (node (ref "SW4") (pin "2") (pinfunction "2_2") (pintype "passive"))
      (node (ref "SW4") (pin "5") (pinfunction "5_5") (pintype "passive"))
    )
    (net (code "30") (name "/RTS") (class "Default")
      (node (ref "Q1") (pin "2") (pinfunction "E_2") (pintype "passive"))
      (node (ref "R10") (pin "1") (pinfunction "1_1") (pintype "passive"))
      (node (ref "U9") (pin "6") (pinfunction "RTS#_6") (pintype "passive"))
    )
    (net (code "31") (name "/SCL") (class "Default")
      (node (ref "R16") (pin "1") (pinfunction "1_1") (pintype "passive"))
      (node (ref "U1") (pin "7") (pinfunction "IO7_7") (pintype "bidirectional"))
      (node (ref "U10") (pin "4") (pinfunction "SCL_4") (pintype "passive"))
      (node (ref "U7") (pin "16") (pinfunction "SCL_16") (pintype "passive"))
    )
    (net (code "32") (name "/SDA") (class "Default")
      (node (ref "R15") (pin "1") (pinfunction "1_1") (pintype "passive"))
      (node (ref "U1") (pin "8") (pinfunction "IO15_8") (pintype "bidirectional"))
      (node (ref "U10") (pin "1") (pinfunction "SDA_1") (pintype "passive"))
      (node (ref "U7") (pin "15") (pinfunction "SDA_15") (pintype "passive"))
    )
    (net (code "33") (name "/SW") (class "Default")
      (node (ref "H2") (pin "4") (pinfunction "4_4") (pintype "passive"))
      (node (ref "U1") (pin "18") (pinfunction "IO10_18") (pintype "bidirectional"))
    )
    (net (code "34") (name "/Sleep_SW") (class "Default")
      (node (ref "C23") (pin "2") (pinfunction "2_2") (pintype "passive"))
      (node (ref "R20") (pin "1") (pinfunction "1_1") (pintype "passive"))
      (node (ref "U1") (pin "15") (pinfunction "IO3_15") (pintype "bidirectional"))
    )
    (net (code "35") (name "/U0RXD") (class "Default")
      (node (ref "U1") (pin "36") (pinfunction "RXD0_36") (pintype "bidirectional"))
      (node (ref "U9") (pin "8") (pinfunction "TXD_8") (pintype "passive"))
    )
    (net (code "36") (name "/U0TXD") (class "Default")
      (node (ref "R21") (pin "1") (pinfunction "1_1") (pintype "passive"))
      (node (ref "U1") (pin "37") (pinfunction "TXD0_37") (pintype "bidirectional"))
      (node (ref "U9") (pin "9") (pinfunction "RXD_9") (pintype "passive"))
    )
    (net (code "37") (name "GND") (class "Default")
      (node (ref "C1") (pin "1") (pinfunction "1_1") (pintype "passive"))
      (node (ref "C10") (pin "1") (pinfunction "1_1") (pintype "passive"))
      (node (ref "C11") (pin "1") (pinfunction "1_1") (pintype "passive"))
      (node (ref "C12") (pin "1") (pinfunction "1_1") (pintype "passive"))
      (node (ref "C13") (pin "1") (pinfunction "1_1") (pintype "passive"))
      (node (ref "C14") (pin "1") (pinfunction "1_1") (pintype "passive"))
      (node (ref "C16") (pin "1") (pinfunction "1_1") (pintype "passive"))
      (node (ref "C18") (pin "1") (pinfunction "1_1") (pintype "passive"))
      (node (ref "C19") (pin "1") (pinfunction "1_1") (pintype "passive"))
      (node (ref "C2") (pin "1") (pinfunction "1_1") (pintype "passive"))
      (node (ref "C20") (pin "1") (pinfunction "1_1") (pintype "passive"))
      (node (ref "C21") (pin "1") (pinfunction "1_1") (pintype "passive"))
      (node (ref "C22") (pin "1") (pinfunction "1_1") (pintype "passive"))
      (node (ref "C23") (pin "1") (pinfunction "1_1") (pintype "passive"))
      (node (ref "C24") (pin "1") (pinfunction "1_1") (pintype "passive"))
      (node (ref "C25") (pin "1") (pinfunction "1_1") (pintype "passive"))
      (node (ref "C26") (pin "1") (pinfunction "1_1") (pintype "passive"))
      (node (ref "C3") (pin "1") (pinfunction "1_1") (pintype "passive"))
      (node (ref "C4") (pin "1") (pinfunction "1_1") (pintype "passive"))
      (node (ref "C5") (pin "1") (pinfunction "1_1") (pintype "passive"))
      (node (ref "C6") (pin "1") (pinfunction "1_1") (pintype "passive"))
      (node (ref "C7") (pin "1") (pinfunction "1_1") (pintype "passive"))
      (node (ref "C8") (pin "1") (pinfunction "1_1") (pintype "passive"))
      (node (ref "C9") (pin "1") (pinfunction "1_1") (pintype "passive"))
      (node (ref "D2") (pin "1") (pinfunction "1_1") (pintype "passive"))
      (node (ref "D3") (pin "1") (pinfunction "1_1") (pintype "passive"))
      (node (ref "D4") (pin "1") (pinfunction "1_1") (pintype "passive"))
      (node (ref "H1") (pin "5") (pinfunction "5_5") (pintype "passive"))
      (node (ref "H1") (pin "6") (pinfunction "6_6") (pintype "passive"))
      (node (ref "LED1") (pin "1") (pinfunction "K_1") (pintype "passive"))
      (node (ref "LED2") (pin "1") (pinfunction "K_1") (pintype "passive"))
      (node (ref "LED3") (pin "1") (pinfunction "K_1") (pintype "passive"))
      (node (ref "MIC1") (pin "2") (pinfunction "2_2") (pintype "passive"))
      (node (ref "P1") (pin "2") (pinfunction "2_2") (pintype "passive"))
      (node (ref "Q3") (pin "2") (pinfunction "E_2") (pintype "passive"))
      (node (ref "R12") (pin "1") (pinfunction "1_1") (pintype "passive"))
      (node (ref "RP1") (pin "3") (pinfunction "3_3") (pintype "passive"))
      (node (ref "SW1") (pin "3") (pinfunction "3_3") (pintype "passive"))
      (node (ref "SW1") (pin "6") (pinfunction "6_6") (pintype "passive"))
      (node (ref "SW2") (pin "3") (pinfunction "3_3") (pintype "passive"))
      (node (ref "SW2") (pin "4") (pinfunction "4_4") (pintype "passive"))
      (node (ref "SW3") (pin "1") (pinfunction "1_1") (pintype "passive"))
      (node (ref "SW4") (pin "3") (pinfunction "3_3") (pintype "passive"))
      (node (ref "SW4") (pin "6") (pinfunction "6_6") (pintype "passive"))
      (node (ref "U1") (pin "1") (pinfunction "GND_1") (pintype "passive"))
      (node (ref "U1") (pin "40") (pinfunction "GND_40") (pintype "passive"))
      (node (ref "U1") (pin "41") (pinfunction "GND_41") (pintype "passive"))
      (node (ref "U10") (pin "2") (pinfunction "ADDR_2") (pintype "passive"))
      (node (ref "U10") (pin "7") (pinfunction "R_7") (pintype "passive"))
      (node (ref "U10") (pin "8") (pinfunction "VSS_8") (pintype "passive"))
      (node (ref "U10") (pin "9") (pinfunction "EP_9") (pintype "passive"))
      (node (ref "U2") (pin "2") (pinfunction "GND_2") (pintype "passive"))
      (node (ref "U3") (pin "9") (pinfunction "EP_9") (pintype "passive"))
      (node (ref "U4") (pin "7") (pinfunction "GND_7") (pintype "passive"))
      (node (ref "U5") (pin "2") (pinfunction "GND_2") (pintype "passive"))
      (node (ref "U6") (pin "2") (pinfunction "GND_2") (pintype "passive"))
      (node (ref "U7") (pin "10") (pinfunction "NC_10") (pintype "passive"))
      (node (ref "U7") (pin "11") (pinfunction "NC_11") (pintype "passive"))
      (node (ref "U7") (pin "12") (pinfunction "NC_12") (pintype "passive"))
      (node (ref "U7") (pin "13") (pinfunction "GND_13") (pintype "passive"))
      (node (ref "U7") (pin "14") (pinfunction "VBAT_14") (pintype "passive"))
      (node (ref "U7") (pin "5") (pinfunction "NC_5") (pintype "passive"))
      (node (ref "U7") (pin "6") (pinfunction "NC_6") (pintype "passive"))
      (node (ref "U7") (pin "7") (pinfunction "NC_7") (pintype "passive"))
      (node (ref "U7") (pin "8") (pinfunction "NC_8") (pintype "passive"))
      (node (ref "U7") (pin "9") (pinfunction "NC_9") (pintype "passive"))
      (node (ref "U8") (pin "1") (pinfunction "GND_1") (pintype "passive"))
      (node (ref "U9") (pin "11") (pinfunction "EP_11") (pintype "passive"))
      (node (ref "U9") (pin "3") (pinfunction "GND_3") (pintype "passive"))
      (node (ref "USB1") (pin "17") (pinfunction "EH_17") (pintype "passive"))
      (node (ref "USB1") (pin "18") (pinfunction "EH_18") (pintype "passive"))
      (node (ref "USB1") (pin "19") (pinfunction "EH_19") (pintype "passive"))
      (node (ref "USB1") (pin "20") (pinfunction "EH_20") (pintype "passive"))
      (node (ref "USB1") (pin "A1") (pinfunction "GND_A1") (pintype "passive"))
      (node (ref "USB1") (pin "A12") (pinfunction "GND_A12") (pintype "passive"))
      (node (ref "USB1") (pin "B1") (pinfunction "GND_B1") (pintype "passive"))
      (node (ref "USB1") (pin "B12") (pinfunction "GND_B12") (pintype "passive"))
    )
    (net (code "38") (name "Net-(C12-Pad2)") (class "Default")
      (node (ref "C12") (pin "2") (pinfunction "2_2") (pintype "passive"))
      (node (ref "R6") (pin "1") (pinfunction "1_1") (pintype "passive"))
    )
    (net (code "39") (name "Net-(C15-Pad2)") (class "Default")
      (node (ref "C15") (pin "2") (pinfunction "2_2") (pintype "passive"))
      (node (ref "MIC1") (pin "1") (pinfunction "1_1") (pintype "passive"))
      (node (ref "R8") (pin "1") (pinfunction "1_1") (pintype "passive"))
    )
    (net (code "40") (name "Net-(C18-Pad2)") (class "Default")
      (node (ref "C18") (pin "2") (pinfunction "2_2") (pintype "passive"))
      (node (ref "R14") (pin "1") (pinfunction "1_1") (pintype "passive"))
    )
    (net (code "41") (name "Net-(D5-A)") (class "Default")
      (node (ref "C10") (pin "2") (pinfunction "2_2") (pintype "passive"))
      (node (ref "C11") (pin "2") (pinfunction "2_2") (pintype "passive"))
      (node (ref "D5") (pin "1") (pinfunction "A_1") (pintype "passive"))
      (node (ref "U3") (pin "8") (pinfunction "VOUT_8") (pintype "passive"))
    )
    (net (code "42") (name "Net-(D6-K)") (class "Default")
      (node (ref "D6") (pin "1") (pinfunction "K_1") (pintype "passive"))
      (node (ref "P2") (pin "1") (pinfunction "1_1") (pintype "passive"))
    )
    (net (code "43") (name "Net-(LED1-A)") (class "Default")
      (node (ref "LED1") (pin "2") (pinfunction "A_2") (pintype "passive"))
      (node (ref "R4") (pin "2") (pinfunction "2_2") (pintype "passive"))
    )
    (net (code "44") (name "Net-(LED2-A)") (class "Default")
      (node (ref "LED2") (pin "2") (pinfunction "A_2") (pintype "passive"))
      (node (ref "R5") (pin "1") (pinfunction "1_1") (pintype "passive"))
    )
    (net (code "45") (name "Net-(LED3-A)") (class "Default")
      (node (ref "LED3") (pin "2") (pinfunction "A_2") (pintype "passive"))
      (node (ref "R18") (pin "2") (pinfunction "2_2") (pintype "passive"))
    )
    (net (code "46") (name "Net-(Q1-B)") (class "Default")
      (node (ref "Q1") (pin "1") (pinfunction "B_1") (pintype "passive"))
      (node (ref "R7") (pin "2") (pinfunction "2_2") (pintype "passive"))
    )
    (net (code "47") (name "Net-(Q2-B)") (class "Default")
      (node (ref "Q2") (pin "1") (pinfunction "B_1") (pintype "passive"))
      (node (ref "R10") (pin "2") (pinfunction "2_2") (pintype "passive"))
    )
    (net (code "48") (name "Net-(Q3-B)") (class "Default")
      (node (ref "C26") (pin "2") (pinfunction "2_2") (pintype "passive"))
      (node (ref "Q3") (pin "1") (pinfunction "B_1") (pintype "passive"))
      (node (ref "R22") (pin "2") (pinfunction "2_2") (pintype "passive"))
    )
    (net (code "49") (name "Net-(Q3-C)") (class "Default")
      (node (ref "P2") (pin "2") (pinfunction "2_2") (pintype "passive"))
      (node (ref "Q3") (pin "3") (pinfunction "C_3") (pintype "passive"))
    )
    (net (code "50") (name "Net-(R11-Pad3)") (class "Default")
      (node (ref "R11") (pin "3") (pinfunction "3_3") (pintype "passive"))
      (node (ref "R13") (pin "2") (pinfunction "2_2") (pintype "passive"))
    )
    (net (code "51") (name "Net-(U1-IO47)") (class "Default")
      (node (ref "R4") (pin "1") (pinfunction "1_1") (pintype "passive"))
      (node (ref "U1") (pin "24") (pinfunction "IO47_24") (pintype "bidirectional"))
    )
    (net (code "52") (name "Net-(U2-EN{slash}EN#)") (class "Default")
      (node (ref "C2") (pin "2") (pinfunction "2_2") (pintype "passive"))
      (node (ref "R3") (pin "1") (pinfunction "1_1") (pintype "passive"))
      (node (ref "U2") (pin "4") (pinfunction "EN/EN#_4") (pintype "passive"))
    )
    (net (code "53") (name "Net-(U3-LED1)") (class "Default")
      (node (ref "R5") (pin "2") (pinfunction "2_2") (pintype "passive"))
      (node (ref "U3") (pin "2") (pinfunction "LED1_2") (pintype "passive"))
    )
    (net (code "54") (name "Net-(U3-SW)") (class "Default")
      (node (ref "L1") (pin "1") (pinfunction "1_1") (pintype "passive"))
      (node (ref "U3") (pin "7") (pinfunction "SW_7") (pintype "passive"))
    )
    (net (code "55") (name "Net-(U5-IN+)") (class "Default")
      (node (ref "C15") (pin "1") (pinfunction "1_1") (pintype "passive"))
      (node (ref "R12") (pin "2") (pinfunction "2_2") (pintype "passive"))
      (node (ref "R9") (pin "1") (pinfunction "1_1") (pintype "passive"))
      (node (ref "U5") (pin "1") (pinfunction "IN+_1") (pintype "passive"))
    )
    (net (code "56") (name "Net-(U5-IN-)") (class "Default")
      (node (ref "C17") (pin "2") (pinfunction "2_2") (pintype "passive"))
      (node (ref "R13") (pin "1") (pinfunction "1_1") (pintype "passive"))
      (node (ref "R14") (pin "2") (pinfunction "2_2") (pintype "passive"))
      (node (ref "U5") (pin "3") (pinfunction "IN-_3") (pintype "passive"))
    )
    (net (code "57") (name "Net-(U5-OUT)") (class "Default")
      (node (ref "C17") (pin "1") (pinfunction "1_1") (pintype "passive"))
      (node (ref "R11") (pin "2") (pinfunction "2_2") (pintype "passive"))
      (node (ref "U5") (pin "4") (pinfunction "OUT_4") (pintype "passive"))
      (node (ref "U6") (pin "3") (pinfunction "IN+_3") (pintype "passive"))
    )
    (net (code "58") (name "Net-(U6-IN-)") (class "Default")
      (node (ref "RP1") (pin "2") (pinfunction "2_2") (pintype "passive"))
      (node (ref "U6") (pin "4") (pinfunction "IN-_4") (pintype "passive"))
    )
    (net (code "59") (name "VBAT") (class "Default")
      (node (ref "C9") (pin "2") (pinfunction "2_2") (pintype "passive"))
      (node (ref "L1") (pin "2") (pinfunction "2_2") (pintype "passive"))
      (node (ref "P1") (pin "1") (pinfunction "1_1") (pintype "passive"))
      (node (ref "U3") (pin "3") (pinfunction "LED2_3") (pintype "passive"))
      (node (ref "U3") (pin "4") (pinfunction "LED3_4") (pintype "passive"))
      (node (ref "U3") (pin "6") (pinfunction "BAT_6") (pintype "passive"))
    )
    (net (code "60") (name "VIN") (class "Default")
      (node (ref "C6") (pin "2") (pinfunction "2_2") (pintype "passive"))
      (node (ref "D1") (pin "1") (pinfunction "A_1") (pintype "passive"))
      (node (ref "D2") (pin "2") (pinfunction "2_2") (pintype "passive"))
      (node (ref "R6") (pin "2") (pinfunction "2_2") (pintype "passive"))
      (node (ref "U3") (pin "1") (pinfunction "VIN_1") (pintype "passive"))
      (node (ref "USB1") (pin "A4") (pinfunction "VBUS_A4") (pintype "passive"))
      (node (ref "USB1") (pin "A9") (pinfunction "VBUS_A9") (pintype "passive"))
      (node (ref "USB1") (pin "B4") (pinfunction "VBUS_B4") (pintype "passive"))
      (node (ref "USB1") (pin "B9") (pinfunction "VBUS_B9") (pintype "passive"))
    )
    (net (code "61") (name "unconnected-(R11-Pad1)") (class "Default")
      (node (ref "R11") (pin "1") (pinfunction "1_1") (pintype "passive+no_connect"))
    )
    (net (code "62") (name "unconnected-(SW2-Pad1)") (class "Default")
      (node (ref "SW2") (pin "1") (pinfunction "1_1") (pintype "passive"))
    )
    (net (code "63") (name "unconnected-(U1-IO2-Pad38)") (class "Default")
      (node (ref "U1") (pin "38") (pinfunction "IO2_38") (pintype "bidirectional+no_connect"))
    )
    (net (code "64") (name "unconnected-(U1-IO19-Pad13)") (class "Default")
      (node (ref "U1") (pin "13") (pinfunction "IO19_13") (pintype "bidirectional+no_connect"))
    )
    (net (code "65") (name "unconnected-(U1-IO20-Pad14)") (class "Default")
      (node (ref "U1") (pin "14") (pinfunction "IO20_14") (pintype "bidirectional+no_connect"))
    )
    (net (code "66") (name "unconnected-(U1-IO35-Pad28)") (class "Default")
      (node (ref "U1") (pin "28") (pinfunction "IO35_28") (pintype "bidirectional+no_connect"))
    )
    (net (code "67") (name "unconnected-(U1-IO36-Pad29)") (class "Default")
      (node (ref "U1") (pin "29") (pinfunction "IO36_29") (pintype "bidirectional+no_connect"))
    )
    (net (code "68") (name "unconnected-(U1-IO37-Pad30)") (class "Default")
      (node (ref "U1") (pin "30") (pinfunction "IO37_30") (pintype "bidirectional+no_connect"))
    )
    (net (code "69") (name "unconnected-(U1-IO38-Pad31)") (class "Default")
      (node (ref "U1") (pin "31") (pinfunction "IO38_31") (pintype "bidirectional+no_connect"))
    )
    (net (code "70") (name "unconnected-(U1-IO39-Pad32)") (class "Default")
      (node (ref "U1") (pin "32") (pinfunction "IO39_32") (pintype "bidirectional+no_connect"))
    )
    (net (code "71") (name "unconnected-(U1-IO40-Pad33)") (class "Default")
      (node (ref "U1") (pin "33") (pinfunction "IO40_33") (pintype "bidirectional+no_connect"))
    )
    (net (code "72") (name "unconnected-(U1-IO41-Pad34)") (class "Default")
      (node (ref "U1") (pin "34") (pinfunction "IO41_34") (pintype "bidirectional+no_connect"))
    )
    (net (code "73") (name "unconnected-(U1-IO42-Pad35)") (class "Default")
      (node (ref "U1") (pin "35") (pinfunction "IO42_35") (pintype "bidirectional+no_connect"))
    )
    (net (code "74") (name "unconnected-(U1-IO45-Pad26)") (class "Default")
      (node (ref "U1") (pin "26") (pinfunction "IO45_26") (pintype "bidirectional+no_connect"))
    )
    (net (code "75") (name "unconnected-(U1-IO48-Pad25)") (class "Default")
      (node (ref "U1") (pin "25") (pinfunction "IO48_25") (pintype "bidirectional+no_connect"))
    )
    (net (code "76") (name "unconnected-(U2-FLT#-Pad3)") (class "Default")
      (node (ref "U2") (pin "3") (pinfunction "FLT#_3") (pintype "passive+no_connect"))
    )
    (net (code "77") (name "unconnected-(U3-KEY-Pad5)") (class "Default")
      (node (ref "U3") (pin "5") (pinfunction "KEY_5") (pintype "passive+no_connect"))
    )
    (net (code "78") (name "unconnected-(U4-NC-Pad6)") (class "Default")
      (node (ref "U4") (pin "6") (pinfunction "NC_6") (pintype "passive+no_connect"))
    )
    (net (code "79") (name "unconnected-(U4-NC-Pad9)") (class "Default")
      (node (ref "U4") (pin "9") (pinfunction "NC_9") (pintype "passive+no_connect"))
    )
    (net (code "80") (name "unconnected-(U7-32kHz-Pad1)") (class "Default")
      (node (ref "U7") (pin "1") (pinfunction "32kHz_1") (pintype "passive+no_connect"))
    )
    (net (code "81") (name "unconnected-(U7-RST-Pad4)") (class "Default")
      (node (ref "U7") (pin "4") (pinfunction "RST_4") (pintype "passive+no_connect"))
    )
    (net (code "82") (name "unconnected-(U9-CTS#-Pad5)") (class "Default")
      (node (ref "U9") (pin "5") (pinfunction "CTS#_5") (pintype "passive+no_connect"))
    )
    (net (code "83") (name "unconnected-(U10-ALERT-Pad3)") (class "Default")
      (node (ref "U10") (pin "3") (pinfunction "ALERT_3") (pintype "passive+no_connect"))
    )
    (net (code "84") (name "unconnected-(U10-nRESET-Pad6)") (class "Default")
      (node (ref "U10") (pin "6") (pinfunction "nRESET_6") (pintype "passive+no_connect"))
    )
    (net (code "85") (name "unconnected-(USB1-CC1-PadA5)") (class "Default")
      (node (ref "USB1") (pin "A5") (pinfunction "CC1_A5") (pintype "passive+no_connect"))
    )
    (net (code "86") (name "unconnected-(USB1-CC2-PadB5)") (class "Default")
      (node (ref "USB1") (pin "B5") (pinfunction "CC2_B5") (pintype "passive+no_connect"))
    )
    (net (code "87") (name "unconnected-(USB1-SBU1-PadA8)") (class "Default")
      (node (ref "USB1") (pin "A8") (pinfunction "SBU1_A8") (pintype "passive+no_connect"))
    )
    (net (code "88") (name "unconnected-(USB1-SBU2-PadB8)") (class "Default")
      (node (ref "USB1") (pin "B8") (pinfunction "SBU2_B8") (pintype "passive+no_connect"))
    )
  )
)
